# Header.net
KiCad netlist of a schematic drawn in Altium Designer
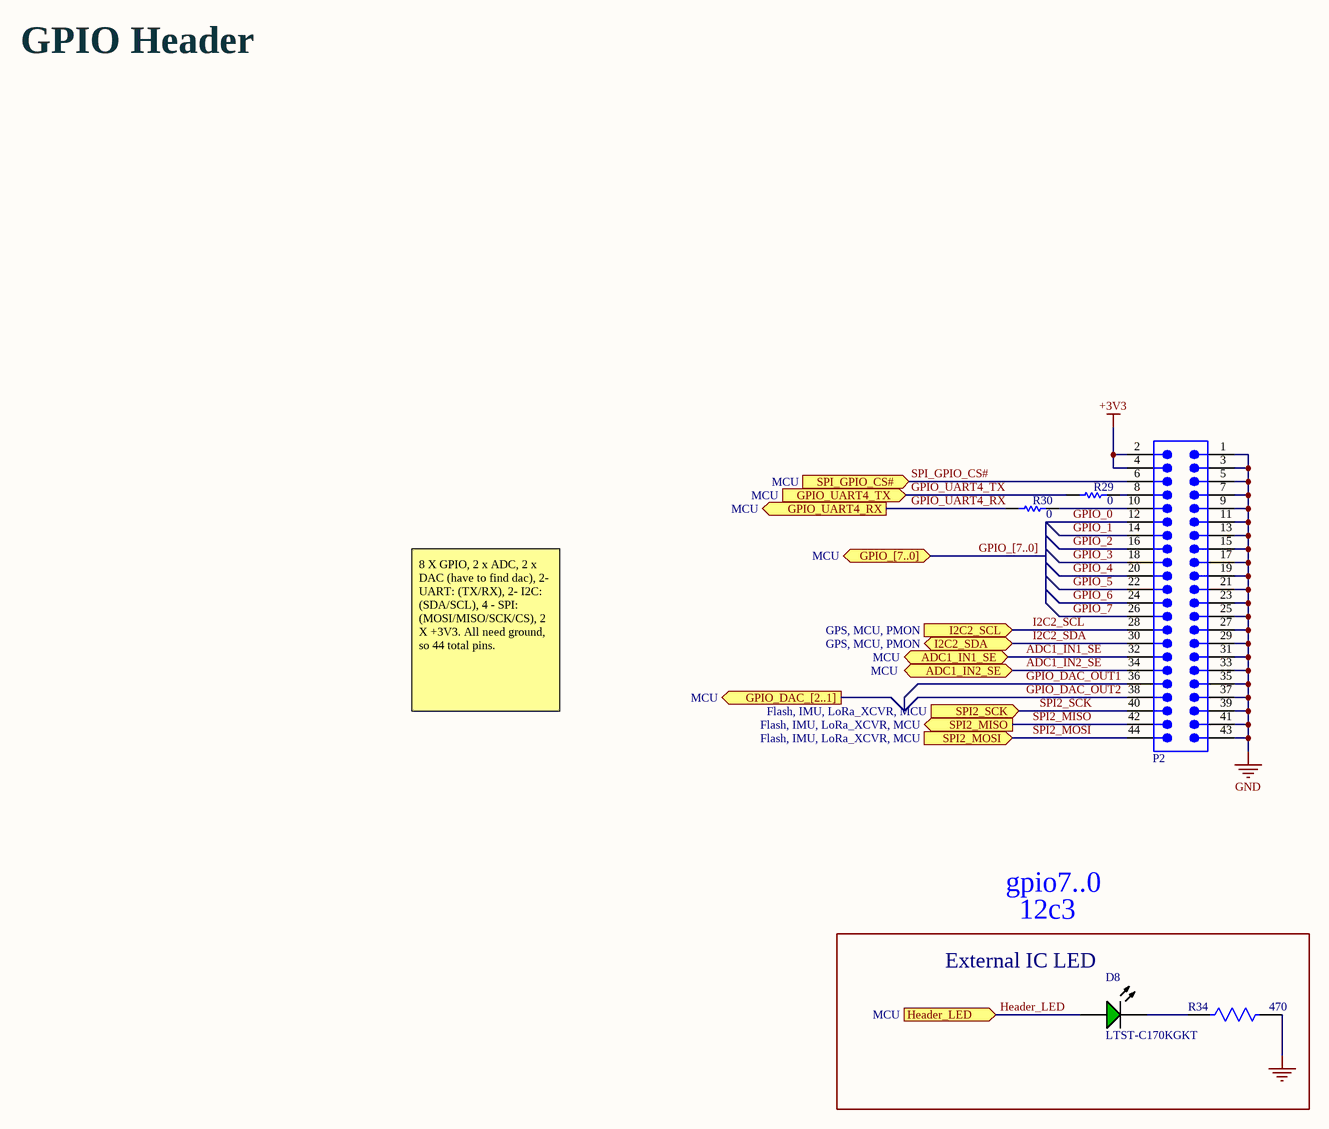
[diagram p0: Header.SchDoc]

(export (version "E")
  (design (tool "Eeschema 10.0.6"))
  (components
    (comp (ref "D8")
      (value "LTST-C170KGKT")
      (footprint "LTST-LTST-C170KGKT-2_V")
      (description "Ultra Bright AlInGaP Chip LED, 75 mW, -55 to 85 degC, 2-Pin SMD (0805), RoHS, Tape and Reel")
      (fields (field (name "MANUFACTURER") "Lite-On"))
      (libsource (lib "Altium Content Vault") (part "LED-GREEN-KA-2"))
    )
    (comp (ref "P2")
      (value "62004421121")
      (footprint "62004421121")
      (libsource (lib "Altium Content Vault") (part "Header_Male_2R_44P"))
    )
    (comp (ref "R29")
      (value "0")
      (footprint "RESC1005X40X25LL05T05")
      (description "Chip Resistor, 0 Ohm, 0.1 W, -55 to 155 degC, 0402 (1005 Metric), RoHS, Tape and Reel")
      (fields (field (name "MANUFACTURER") "Panasonic") (field (name "TOLERANCE") "5%"))
      (libsource (lib "Altium Content Vault") (part "RES-2"))
    )
    (comp (ref "R30")
      (value "0")
      (footprint "RESC1005X40X25LL05T05")
      (description "Chip Resistor, 0 Ohm, 0.1 W, -55 to 155 degC, 0402 (1005 Metric), RoHS, Tape and Reel")
      (fields (field (name "MANUFACTURER") "Panasonic") (field (name "TOLERANCE") "5%"))
      (libsource (lib "Altium Content Vault") (part "RES-2"))
    )
    (comp (ref "R34")
      (value "470")
      (footprint "FP-CPF0603-MFG")
      (description "RES SMD 470Ω 0.1% 1/16W 0603\r\n\r\nCPF0603B470RE")
      (fields
        (field (name "MANUFACTURER") "TE Connectivity")
        (field (name "MANUFACTURER PART NUMBER") "CPF0603B470RE")
      )
      (libsource (lib "Altium Content Vault") (part "1029c3af85768c4190bb7ad29bc67b5"))
    )
  )
  (nets
    (net (code "3") (name "+3V3") (class "Default")
      (node (ref "P2") (pin "2") (pinfunction "2_2") (pintype "passive"))
      (node (ref "P2") (pin "4") (pinfunction "4_4") (pintype "passive"))
    )
    (net (code "4") (name "/ADC1_IN1_SE") (class "Default")
      (node (ref "P2") (pin "32") (pinfunction "32_32") (pintype "passive"))
    )
    (net (code "5") (name "/ADC1_IN2_SE") (class "Default")
      (node (ref "P2") (pin "34") (pinfunction "34_34") (pintype "passive"))
    )
    (net (code "6") (name "/GPIO_0") (class "Default")
      (node (ref "P2") (pin "12") (pinfunction "12_12") (pintype "passive"))
    )
    (net (code "7") (name "/GPIO_1") (class "Default")
      (node (ref "P2") (pin "14") (pinfunction "14_14") (pintype "passive"))
    )
    (net (code "8") (name "/GPIO_2") (class "Default")
      (node (ref "P2") (pin "16") (pinfunction "16_16") (pintype "passive"))
    )
    (net (code "9") (name "/GPIO_3") (class "Default")
      (node (ref "P2") (pin "18") (pinfunction "18_18") (pintype "passive"))
    )
    (net (code "10") (name "/GPIO_4") (class "Default")
      (node (ref "P2") (pin "20") (pinfunction "20_20") (pintype "passive"))
    )
    (net (code "11") (name "/GPIO_5") (class "Default")
      (node (ref "P2") (pin "22") (pinfunction "22_22") (pintype "passive"))
    )
    (net (code "12") (name "/GPIO_6") (class "Default")
      (node (ref "P2") (pin "24") (pinfunction "24_24") (pintype "passive"))
    )
    (net (code "13") (name "/GPIO_7") (class "Default")
      (node (ref "P2") (pin "26") (pinfunction "26_26") (pintype "passive"))
    )
    (net (code "14") (name "/GPIO_DAC_OUT1") (class "Default")
      (node (ref "P2") (pin "36") (pinfunction "36_36") (pintype "passive"))
    )
    (net (code "15") (name "/GPIO_DAC_OUT2") (class "Default")
      (node (ref "P2") (pin "38") (pinfunction "38_38") (pintype "passive"))
    )
    (net (code "17") (name "/GPIO_UART4_RX") (class "Default")
      (node (ref "R30") (pin "2") (pinfunction "2_2") (pintype "passive"))
    )
    (net (code "18") (name "/GPIO_UART4_TX") (class "Default")
      (node (ref "R29") (pin "2") (pinfunction "2_2") (pintype "passive"))
    )
    (net (code "20") (name "/Header_LED") (class "Default")
      (node (ref "D8") (pin "2") (pinfunction "A_2") (pintype "passive"))
    )
    (net (code "21") (name "/I2C2_SCL") (class "Default")
      (node (ref "P2") (pin "28") (pinfunction "28_28") (pintype "passive"))
    )
    (net (code "22") (name "/I2C2_SDA") (class "Default")
      (node (ref "P2") (pin "30") (pinfunction "30_30") (pintype "passive"))
    )
    (net (code "23") (name "/SPI2_MISO") (class "Default")
      (node (ref "P2") (pin "42") (pinfunction "42_42") (pintype "passive"))
    )
    (net (code "24") (name "/SPI2_MOSI") (class "Default")
      (node (ref "P2") (pin "44") (pinfunction "44_44") (pintype "passive"))
    )
    (net (code "25") (name "/SPI2_SCK") (class "Default")
      (node (ref "P2") (pin "40") (pinfunction "40_40") (pintype "passive"))
    )
    (net (code "26") (name "/SPI_GPIO_CS#") (class "Default")
      (node (ref "P2") (pin "6") (pinfunction "6_6") (pintype "passive"))
    )
    (net (code "27") (name "GND") (class "Default")
      (node (ref "P2") (pin "1") (pinfunction "1_1") (pintype "passive"))
      (node (ref "P2") (pin "11") (pinfunction "11_11") (pintype "passive"))
      (node (ref "P2") (pin "13") (pinfunction "13_13") (pintype "passive"))
      (node (ref "P2") (pin "15") (pinfunction "15_15") (pintype "passive"))
      (node (ref "P2") (pin "17") (pinfunction "17_17") (pintype "passive"))
      (node (ref "P2") (pin "19") (pinfunction "19_19") (pintype "passive"))
      (node (ref "P2") (pin "21") (pinfunction "21_21") (pintype "passive"))
      (node (ref "P2") (pin "23") (pinfunction "23_23") (pintype "passive"))
      (node (ref "P2") (pin "25") (pinfunction "25_25") (pintype "passive"))
      (node (ref "P2") (pin "27") (pinfunction "27_27") (pintype "passive"))
      (node (ref "P2") (pin "29") (pinfunction "29_29") (pintype "passive"))
      (node (ref "P2") (pin "3") (pinfunction "3_3") (pintype "passive"))
      (node (ref "P2") (pin "31") (pinfunction "31_31") (pintype "passive"))
      (node (ref "P2") (pin "33") (pinfunction "33_33") (pintype "passive"))
      (node (ref "P2") (pin "35") (pinfunction "35_35") (pintype "passive"))
      (node (ref "P2") (pin "37") (pinfunction "37_37") (pintype "passive"))
      (node (ref "P2") (pin "39") (pinfunction "39_39") (pintype "passive"))
      (node (ref "P2") (pin "41") (pinfunction "41_41") (pintype "passive"))
      (node (ref "P2") (pin "43") (pinfunction "43_43") (pintype "passive"))
      (node (ref "P2") (pin "5") (pinfunction "5_5") (pintype "passive"))
      (node (ref "P2") (pin "7") (pinfunction "7_7") (pintype "passive"))
      (node (ref "P2") (pin "9") (pinfunction "9_9") (pintype "passive"))
      (node (ref "R34") (pin "2") (pinfunction "2_2") (pintype "passive"))
    )
    (net (code "28") (name "Net-(D8-K)") (class "Default")
      (node (ref "D8") (pin "1") (pinfunction "K_1") (pintype "passive"))
      (node (ref "R34") (pin "1") (pinfunction "1_1") (pintype "passive"))
    )
    (net (code "29") (name "Net-(P2-Pad8)") (class "Default")
      (node (ref "P2") (pin "8") (pinfunction "8_8") (pintype "passive"))
      (node (ref "R29") (pin "1") (pinfunction "1_1") (pintype "passive"))
    )
    (net (code "30") (name "Net-(P2-Pad10)") (class "Default")
      (node (ref "P2") (pin "10") (pinfunction "10_10") (pintype "passive"))
      (node (ref "R30") (pin "1") (pinfunction "1_1") (pintype "passive"))
    )
  )
)
